# drive_trifasico.net
KiCad netlist of a schematic drawn in EAGLE
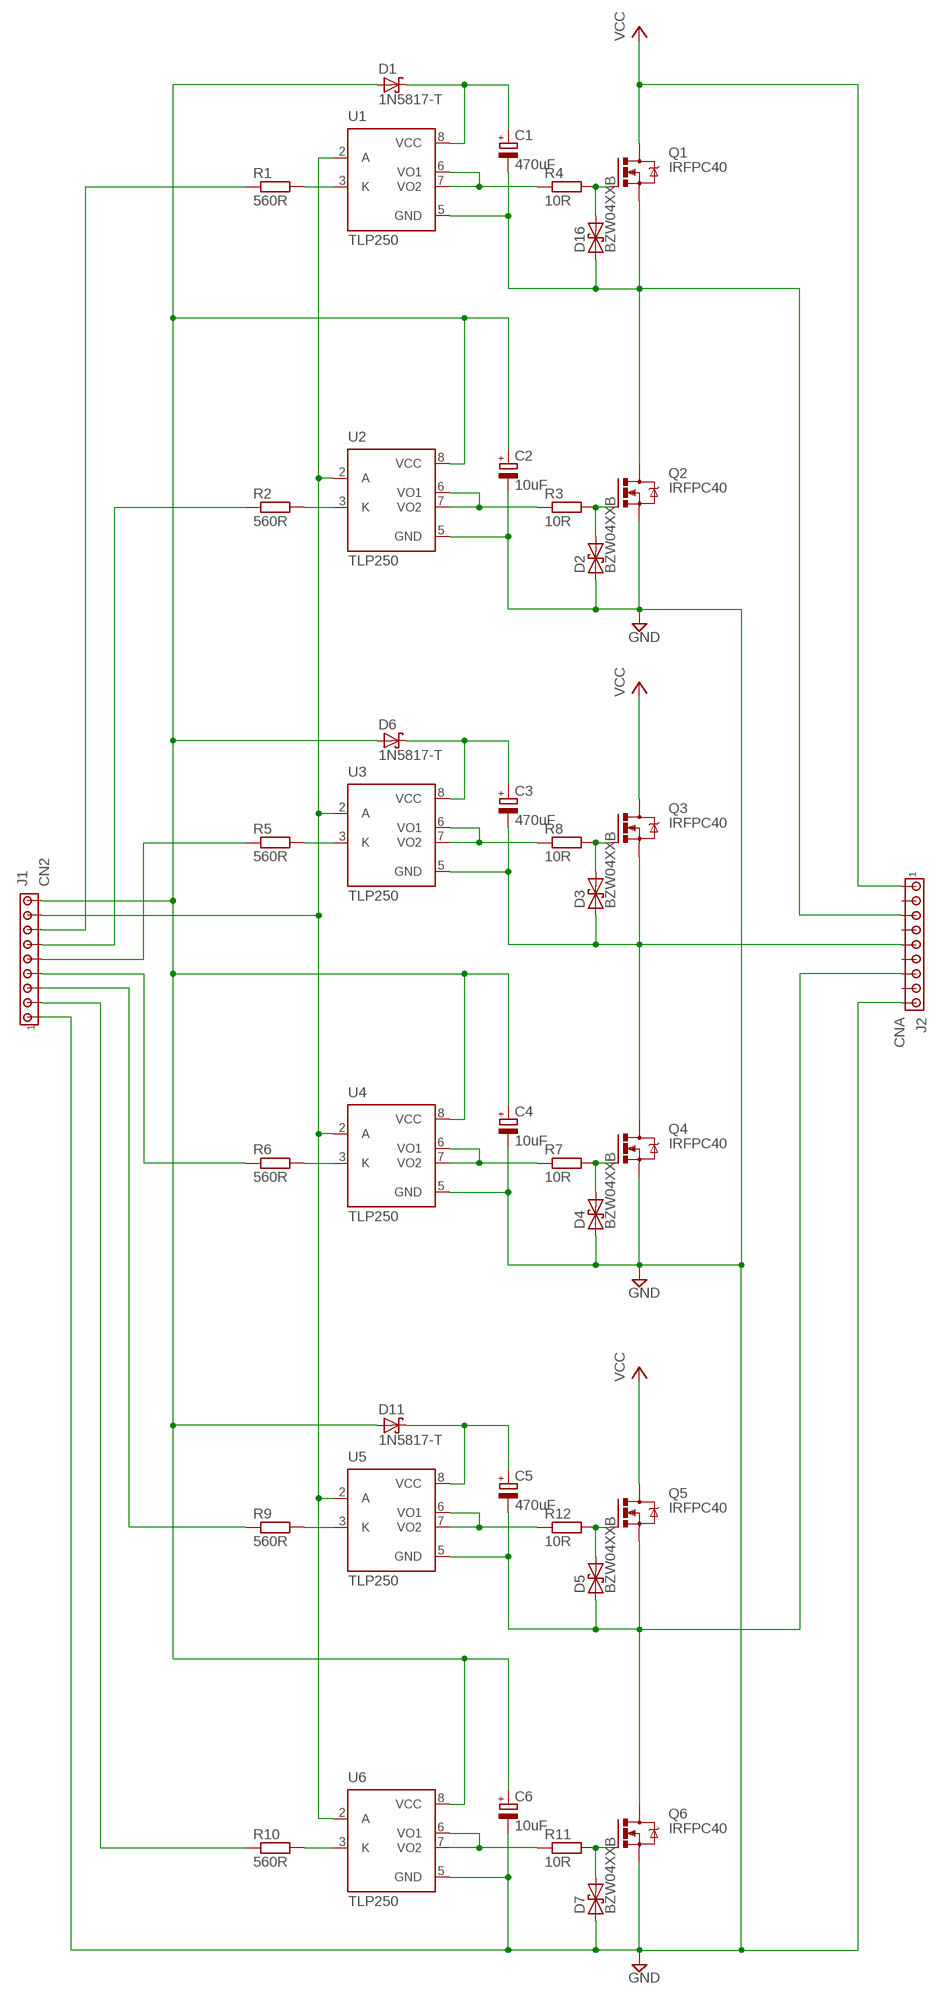
[diagram p0: schematic, sheet 1]

(export (version "E")
  (design (tool "Eeschema 10.0.6"))
  (components
    (comp (ref "C1")
      (value "470uF")
      (footprint "eagle-import:E5-8,5")
      (libsource (lib "eagle-import") (part "CPOL-EUE5-8.5"))
    )
    (comp (ref "C2")
      (value "10uF")
      (footprint "eagle-import:E5-6")
      (libsource (lib "eagle-import") (part "CPOL-EUE5-6"))
    )
    (comp (ref "C3")
      (value "470uF")
      (footprint "eagle-import:E5-8,5")
      (libsource (lib "eagle-import") (part "CPOL-EUE5-8.5"))
    )
    (comp (ref "C4")
      (value "10uF")
      (footprint "eagle-import:E5-6")
      (libsource (lib "eagle-import") (part "CPOL-EUE5-6"))
    )
    (comp (ref "C5")
      (value "470uF")
      (footprint "eagle-import:E5-8,5")
      (libsource (lib "eagle-import") (part "CPOL-EUE5-8.5"))
    )
    (comp (ref "C6")
      (value "10uF")
      (footprint "eagle-import:E5-6")
      (libsource (lib "eagle-import") (part "CPOL-EUE5-6"))
    )
    (comp (ref "D1")
      (value "1N5817-T")
      (footprint "eagle-import:DO41-7.6")
      (libsource (lib "eagle-import") (part "1N5817-T"))
    )
    (comp (ref "D2")
      (value "BZW04XXB")
      (footprint "eagle-import:F126Z12")
      (libsource (lib "eagle-import") (part "BZW04XXB"))
    )
    (comp (ref "D3")
      (value "BZW04XXB")
      (footprint "eagle-import:F126Z12")
      (libsource (lib "eagle-import") (part "BZW04XXB"))
    )
    (comp (ref "D4")
      (value "BZW04XXB")
      (footprint "eagle-import:F126Z12")
      (libsource (lib "eagle-import") (part "BZW04XXB"))
    )
    (comp (ref "D5")
      (value "BZW04XXB")
      (footprint "eagle-import:F126Z12")
      (libsource (lib "eagle-import") (part "BZW04XXB"))
    )
    (comp (ref "D6")
      (value "1N5817-T")
      (footprint "eagle-import:DO41-7.6")
      (libsource (lib "eagle-import") (part "1N5817-T"))
    )
    (comp (ref "D7")
      (value "BZW04XXB")
      (footprint "eagle-import:F126Z12")
      (libsource (lib "eagle-import") (part "BZW04XXB"))
    )
    (comp (ref "D11")
      (value "1N5817-T")
      (footprint "eagle-import:DO41-7.6")
      (libsource (lib "eagle-import") (part "1N5817-T"))
    )
    (comp (ref "D16")
      (value "BZW04XXB")
      (footprint "eagle-import:F126Z12")
      (libsource (lib "eagle-import") (part "BZW04XXB"))
    )
    (comp (ref "J1")
      (value "CN2")
      (footprint "eagle-import:10X09MTA")
      (libsource (lib "eagle-import") (part "MTA09-100"))
    )
    (comp (ref "J2")
      (value "CNA")
      (footprint "eagle-import:1X9MTA")
      (libsource (lib "eagle-import") (part "MTA09-156"))
    )
    (comp (ref "Q1")
      (value "IRFPC40")
      (footprint "eagle-import:TO247BV")
      (libsource (lib "eagle-import") (part "IRFPC40"))
    )
    (comp (ref "Q2")
      (value "IRFPC40")
      (footprint "eagle-import:TO247BV")
      (libsource (lib "eagle-import") (part "IRFPC40"))
    )
    (comp (ref "Q3")
      (value "IRFPC40")
      (footprint "eagle-import:TO247BV")
      (libsource (lib "eagle-import") (part "IRFPC40"))
    )
    (comp (ref "Q4")
      (value "IRFPC40")
      (footprint "eagle-import:TO247BV")
      (libsource (lib "eagle-import") (part "IRFPC40"))
    )
    (comp (ref "Q5")
      (value "IRFPC40")
      (footprint "eagle-import:TO247BV")
      (libsource (lib "eagle-import") (part "IRFPC40"))
    )
    (comp (ref "Q6")
      (value "IRFPC40")
      (footprint "eagle-import:TO247BV")
      (libsource (lib "eagle-import") (part "IRFPC40"))
    )
    (comp (ref "R1")
      (value "560R")
      (footprint "eagle-import:0207_12")
      (libsource (lib "eagle-import") (part "R-EU_0207/12"))
    )
    (comp (ref "R2")
      (value "560R")
      (footprint "eagle-import:0207_12")
      (libsource (lib "eagle-import") (part "R-EU_0207/12"))
    )
    (comp (ref "R3")
      (value "10R")
      (footprint "eagle-import:0207_12")
      (libsource (lib "eagle-import") (part "R-EU_0207/12"))
    )
    (comp (ref "R4")
      (value "10R")
      (footprint "eagle-import:0207_12")
      (libsource (lib "eagle-import") (part "R-EU_0207/12"))
    )
    (comp (ref "R5")
      (value "560R")
      (footprint "eagle-import:0207_12")
      (libsource (lib "eagle-import") (part "R-EU_0207/12"))
    )
    (comp (ref "R6")
      (value "560R")
      (footprint "eagle-import:0207_12")
      (libsource (lib "eagle-import") (part "R-EU_0207/12"))
    )
    (comp (ref "R7")
      (value "10R")
      (footprint "eagle-import:0207_12")
      (libsource (lib "eagle-import") (part "R-EU_0207/12"))
    )
    (comp (ref "R8")
      (value "10R")
      (footprint "eagle-import:0207_12")
      (libsource (lib "eagle-import") (part "R-EU_0207/12"))
    )
    (comp (ref "R9")
      (value "560R")
      (footprint "eagle-import:0207_12")
      (libsource (lib "eagle-import") (part "R-EU_0207/12"))
    )
    (comp (ref "R10")
      (value "560R")
      (footprint "eagle-import:0207_12")
      (libsource (lib "eagle-import") (part "R-EU_0207/12"))
    )
    (comp (ref "R11")
      (value "10R")
      (footprint "eagle-import:0207_12")
      (libsource (lib "eagle-import") (part "R-EU_0207/12"))
    )
    (comp (ref "R12")
      (value "10R")
      (footprint "eagle-import:0207_12")
      (libsource (lib "eagle-import") (part "R-EU_0207/12"))
    )
    (comp (ref "U1")
      (value "TLP250")
      (footprint "eagle-import:DIP08")
      (libsource (lib "eagle-import") (part "TLP250"))
    )
    (comp (ref "U2")
      (value "TLP250")
      (footprint "eagle-import:DIP08")
      (libsource (lib "eagle-import") (part "TLP250"))
    )
    (comp (ref "U3")
      (value "TLP250")
      (footprint "eagle-import:DIP08")
      (libsource (lib "eagle-import") (part "TLP250"))
    )
    (comp (ref "U4")
      (value "TLP250")
      (footprint "eagle-import:DIP08")
      (libsource (lib "eagle-import") (part "TLP250"))
    )
    (comp (ref "U5")
      (value "TLP250")
      (footprint "eagle-import:DIP08")
      (libsource (lib "eagle-import") (part "TLP250"))
    )
    (comp (ref "U6")
      (value "TLP250")
      (footprint "eagle-import:DIP08")
      (libsource (lib "eagle-import") (part "TLP250"))
    )
  )
  (nets
    (net (code "1") (name "GND") (class "Default")
      (node (ref "C2") (pin "-") (pinfunction "-_-") (pintype "passive"))
      (node (ref "C4") (pin "-") (pinfunction "-_-") (pintype "passive"))
      (node (ref "C6") (pin "-") (pinfunction "-_-") (pintype "passive"))
      (node (ref "D2") (pin "A") (pinfunction "1_A") (pintype "passive"))
      (node (ref "D4") (pin "A") (pinfunction "1_A") (pintype "passive"))
      (node (ref "D7") (pin "A") (pinfunction "1_A") (pintype "passive"))
      (node (ref "J1") (pin "1") (pinfunction "1_1") (pintype "passive"))
      (node (ref "J2") (pin "9") (pinfunction "9_9") (pintype "passive"))
      (node (ref "Q2") (pin "S") (pinfunction "S_S") (pintype "passive"))
      (node (ref "Q4") (pin "S") (pinfunction "S_S") (pintype "passive"))
      (node (ref "Q6") (pin "S") (pinfunction "S_S") (pintype "passive"))
      (node (ref "U2") (pin "5") (pinfunction "GND_5") (pintype "power_in"))
      (node (ref "U4") (pin "5") (pinfunction "GND_5") (pintype "power_in"))
      (node (ref "U6") (pin "5") (pinfunction "GND_5") (pintype "power_in"))
    )
    (net (code "2") (name "Net-(D2-2)") (class "Default")
      (node (ref "D2") (pin "C") (pinfunction "2_C") (pintype "passive"))
      (node (ref "Q2") (pin "G") (pinfunction "G_G") (pintype "passive"))
      (node (ref "R3") (pin "2") (pinfunction "2_2") (pintype "passive"))
    )
    (net (code "3") (name "Net-(D3-1)") (class "Default")
      (node (ref "C3") (pin "-") (pinfunction "-_-") (pintype "passive"))
      (node (ref "D3") (pin "A") (pinfunction "1_A") (pintype "passive"))
      (node (ref "J2") (pin "5") (pinfunction "5_5") (pintype "passive"))
      (node (ref "Q3") (pin "S") (pinfunction "S_S") (pintype "passive"))
      (node (ref "Q4") (pin "D") (pinfunction "D_D") (pintype "passive"))
      (node (ref "U3") (pin "5") (pinfunction "GND_5") (pintype "power_in"))
    )
    (net (code "4") (name "Net-(D3-2)") (class "Default")
      (node (ref "D3") (pin "C") (pinfunction "2_C") (pintype "passive"))
      (node (ref "Q3") (pin "G") (pinfunction "G_G") (pintype "passive"))
      (node (ref "R8") (pin "2") (pinfunction "2_2") (pintype "passive"))
    )
    (net (code "5") (name "Net-(D4-2)") (class "Default")
      (node (ref "D4") (pin "C") (pinfunction "2_C") (pintype "passive"))
      (node (ref "Q4") (pin "G") (pinfunction "G_G") (pintype "passive"))
      (node (ref "R7") (pin "2") (pinfunction "2_2") (pintype "passive"))
    )
    (net (code "6") (name "Net-(D5-1)") (class "Default")
      (node (ref "C5") (pin "-") (pinfunction "-_-") (pintype "passive"))
      (node (ref "D5") (pin "A") (pinfunction "1_A") (pintype "passive"))
      (node (ref "J2") (pin "7") (pinfunction "7_7") (pintype "passive"))
      (node (ref "Q5") (pin "S") (pinfunction "S_S") (pintype "passive"))
      (node (ref "Q6") (pin "D") (pinfunction "D_D") (pintype "passive"))
      (node (ref "U5") (pin "5") (pinfunction "GND_5") (pintype "power_in"))
    )
    (net (code "7") (name "Net-(D5-2)") (class "Default")
      (node (ref "D5") (pin "C") (pinfunction "2_C") (pintype "passive"))
      (node (ref "Q5") (pin "G") (pinfunction "G_G") (pintype "passive"))
      (node (ref "R12") (pin "2") (pinfunction "2_2") (pintype "passive"))
    )
    (net (code "8") (name "Net-(D7-2)") (class "Default")
      (node (ref "D7") (pin "C") (pinfunction "2_C") (pintype "passive"))
      (node (ref "Q6") (pin "G") (pinfunction "G_G") (pintype "passive"))
      (node (ref "R11") (pin "2") (pinfunction "2_2") (pintype "passive"))
    )
    (net (code "9") (name "Net-(D16-1)") (class "Default")
      (node (ref "C1") (pin "-") (pinfunction "-_-") (pintype "passive"))
      (node (ref "D16") (pin "A") (pinfunction "1_A") (pintype "passive"))
      (node (ref "J2") (pin "3") (pinfunction "3_3") (pintype "passive"))
      (node (ref "Q1") (pin "S") (pinfunction "S_S") (pintype "passive"))
      (node (ref "Q2") (pin "D") (pinfunction "D_D") (pintype "passive"))
      (node (ref "U1") (pin "5") (pinfunction "GND_5") (pintype "power_in"))
    )
    (net (code "10") (name "Net-(D16-2)") (class "Default")
      (node (ref "D16") (pin "C") (pinfunction "2_C") (pintype "passive"))
      (node (ref "Q1") (pin "G") (pinfunction "G_G") (pintype "passive"))
      (node (ref "R4") (pin "2") (pinfunction "2_2") (pintype "passive"))
    )
    (net (code "11") (name "Net-(J1-Pad2)") (class "Default")
      (node (ref "J1") (pin "2") (pinfunction "2_2") (pintype "passive"))
      (node (ref "R10") (pin "1") (pinfunction "1_1") (pintype "passive"))
    )
    (net (code "12") (name "Net-(J1-Pad3)") (class "Default")
      (node (ref "J1") (pin "3") (pinfunction "3_3") (pintype "passive"))
      (node (ref "R9") (pin "1") (pinfunction "1_1") (pintype "passive"))
    )
    (net (code "13") (name "Net-(J1-Pad4)") (class "Default")
      (node (ref "J1") (pin "4") (pinfunction "4_4") (pintype "passive"))
      (node (ref "R6") (pin "1") (pinfunction "1_1") (pintype "passive"))
    )
    (net (code "14") (name "Net-(J1-Pad5)") (class "Default")
      (node (ref "J1") (pin "5") (pinfunction "5_5") (pintype "passive"))
      (node (ref "R5") (pin "1") (pinfunction "1_1") (pintype "passive"))
    )
    (net (code "15") (name "Net-(J1-Pad6)") (class "Default")
      (node (ref "J1") (pin "6") (pinfunction "6_6") (pintype "passive"))
      (node (ref "R2") (pin "1") (pinfunction "1_1") (pintype "passive"))
    )
    (net (code "16") (name "Net-(J1-Pad7)") (class "Default")
      (node (ref "J1") (pin "7") (pinfunction "7_7") (pintype "passive"))
      (node (ref "R1") (pin "1") (pinfunction "1_1") (pintype "passive"))
    )
    (net (code "17") (name "Net-(U1-A)") (class "Default")
      (node (ref "J1") (pin "8") (pinfunction "8_8") (pintype "passive"))
      (node (ref "U1") (pin "2") (pinfunction "A_2") (pintype "input"))
      (node (ref "U2") (pin "2") (pinfunction "A_2") (pintype "input"))
      (node (ref "U3") (pin "2") (pinfunction "A_2") (pintype "input"))
      (node (ref "U4") (pin "2") (pinfunction "A_2") (pintype "input"))
      (node (ref "U5") (pin "2") (pinfunction "A_2") (pintype "input"))
      (node (ref "U6") (pin "2") (pinfunction "A_2") (pintype "input"))
    )
    (net (code "18") (name "Net-(U1-K)") (class "Default")
      (node (ref "R1") (pin "2") (pinfunction "2_2") (pintype "passive"))
      (node (ref "U1") (pin "3") (pinfunction "K_3") (pintype "input"))
    )
    (net (code "19") (name "Net-(U1-VCC)") (class "Default")
      (node (ref "C1") (pin "+") (pinfunction "+_+") (pintype "passive"))
      (node (ref "D1") (pin "C") (pinfunction "C_C") (pintype "passive"))
      (node (ref "U1") (pin "8") (pinfunction "VCC_8") (pintype "power_in"))
    )
    (net (code "20") (name "Net-(U1-VO1)") (class "Default")
      (node (ref "R4") (pin "1") (pinfunction "1_1") (pintype "passive"))
      (node (ref "U1") (pin "6") (pinfunction "VO1_6") (pintype "output"))
      (node (ref "U1") (pin "7") (pinfunction "VO2_7") (pintype "output"))
    )
    (net (code "21") (name "Net-(U2-K)") (class "Default")
      (node (ref "R2") (pin "2") (pinfunction "2_2") (pintype "passive"))
      (node (ref "U2") (pin "3") (pinfunction "K_3") (pintype "input"))
    )
    (net (code "22") (name "Net-(U2-VCC)") (class "Default")
      (node (ref "C2") (pin "+") (pinfunction "+_+") (pintype "passive"))
      (node (ref "C4") (pin "+") (pinfunction "+_+") (pintype "passive"))
      (node (ref "C6") (pin "+") (pinfunction "+_+") (pintype "passive"))
      (node (ref "D1") (pin "A") (pinfunction "A_A") (pintype "passive"))
      (node (ref "D11") (pin "A") (pinfunction "A_A") (pintype "passive"))
      (node (ref "D6") (pin "A") (pinfunction "A_A") (pintype "passive"))
      (node (ref "J1") (pin "9") (pinfunction "9_9") (pintype "passive"))
      (node (ref "U2") (pin "8") (pinfunction "VCC_8") (pintype "power_in"))
      (node (ref "U4") (pin "8") (pinfunction "VCC_8") (pintype "power_in"))
      (node (ref "U6") (pin "8") (pinfunction "VCC_8") (pintype "power_in"))
    )
    (net (code "23") (name "Net-(U2-VO1)") (class "Default")
      (node (ref "R3") (pin "1") (pinfunction "1_1") (pintype "passive"))
      (node (ref "U2") (pin "6") (pinfunction "VO1_6") (pintype "output"))
      (node (ref "U2") (pin "7") (pinfunction "VO2_7") (pintype "output"))
    )
    (net (code "24") (name "Net-(U3-K)") (class "Default")
      (node (ref "R5") (pin "2") (pinfunction "2_2") (pintype "passive"))
      (node (ref "U3") (pin "3") (pinfunction "K_3") (pintype "input"))
    )
    (net (code "25") (name "Net-(U3-VCC)") (class "Default")
      (node (ref "C3") (pin "+") (pinfunction "+_+") (pintype "passive"))
      (node (ref "D6") (pin "C") (pinfunction "C_C") (pintype "passive"))
      (node (ref "U3") (pin "8") (pinfunction "VCC_8") (pintype "power_in"))
    )
    (net (code "26") (name "Net-(U3-VO1)") (class "Default")
      (node (ref "R8") (pin "1") (pinfunction "1_1") (pintype "passive"))
      (node (ref "U3") (pin "6") (pinfunction "VO1_6") (pintype "output"))
      (node (ref "U3") (pin "7") (pinfunction "VO2_7") (pintype "output"))
    )
    (net (code "27") (name "Net-(U4-K)") (class "Default")
      (node (ref "R6") (pin "2") (pinfunction "2_2") (pintype "passive"))
      (node (ref "U4") (pin "3") (pinfunction "K_3") (pintype "input"))
    )
    (net (code "28") (name "Net-(U4-VO1)") (class "Default")
      (node (ref "R7") (pin "1") (pinfunction "1_1") (pintype "passive"))
      (node (ref "U4") (pin "6") (pinfunction "VO1_6") (pintype "output"))
      (node (ref "U4") (pin "7") (pinfunction "VO2_7") (pintype "output"))
    )
    (net (code "29") (name "Net-(U5-K)") (class "Default")
      (node (ref "R9") (pin "2") (pinfunction "2_2") (pintype "passive"))
      (node (ref "U5") (pin "3") (pinfunction "K_3") (pintype "input"))
    )
    (net (code "30") (name "Net-(U5-VCC)") (class "Default")
      (node (ref "C5") (pin "+") (pinfunction "+_+") (pintype "passive"))
      (node (ref "D11") (pin "C") (pinfunction "C_C") (pintype "passive"))
      (node (ref "U5") (pin "8") (pinfunction "VCC_8") (pintype "power_in"))
    )
    (net (code "31") (name "Net-(U5-VO1)") (class "Default")
      (node (ref "R12") (pin "1") (pinfunction "1_1") (pintype "passive"))
      (node (ref "U5") (pin "6") (pinfunction "VO1_6") (pintype "output"))
      (node (ref "U5") (pin "7") (pinfunction "VO2_7") (pintype "output"))
    )
    (net (code "32") (name "Net-(U6-K)") (class "Default")
      (node (ref "R10") (pin "2") (pinfunction "2_2") (pintype "passive"))
      (node (ref "U6") (pin "3") (pinfunction "K_3") (pintype "input"))
    )
    (net (code "33") (name "Net-(U6-VO1)") (class "Default")
      (node (ref "R11") (pin "1") (pinfunction "1_1") (pintype "passive"))
      (node (ref "U6") (pin "6") (pinfunction "VO1_6") (pintype "output"))
      (node (ref "U6") (pin "7") (pinfunction "VO2_7") (pintype "output"))
    )
    (net (code "34") (name "VCC") (class "Default")
      (node (ref "J2") (pin "1") (pinfunction "1_1") (pintype "passive"))
      (node (ref "Q1") (pin "D") (pinfunction "D_D") (pintype "passive"))
      (node (ref "Q3") (pin "D") (pinfunction "D_D") (pintype "passive"))
      (node (ref "Q5") (pin "D") (pinfunction "D_D") (pintype "passive"))
    )
    (net (code "35") (name "unconnected-(J2-Pad2)") (class "Default")
      (node (ref "J2") (pin "2") (pinfunction "2_2") (pintype "passive"))
    )
    (net (code "36") (name "unconnected-(J2-Pad4)") (class "Default")
      (node (ref "J2") (pin "4") (pinfunction "4_4") (pintype "passive"))
    )
    (net (code "37") (name "unconnected-(J2-Pad6)") (class "Default")
      (node (ref "J2") (pin "6") (pinfunction "6_6") (pintype "passive"))
    )
    (net (code "38") (name "unconnected-(J2-Pad8)") (class "Default")
      (node (ref "J2") (pin "8") (pinfunction "8_8") (pintype "passive"))
    )
  )
)
